# FET_Driver_Shunts.net
KiCad netlist of a schematic drawn in Altium Designer
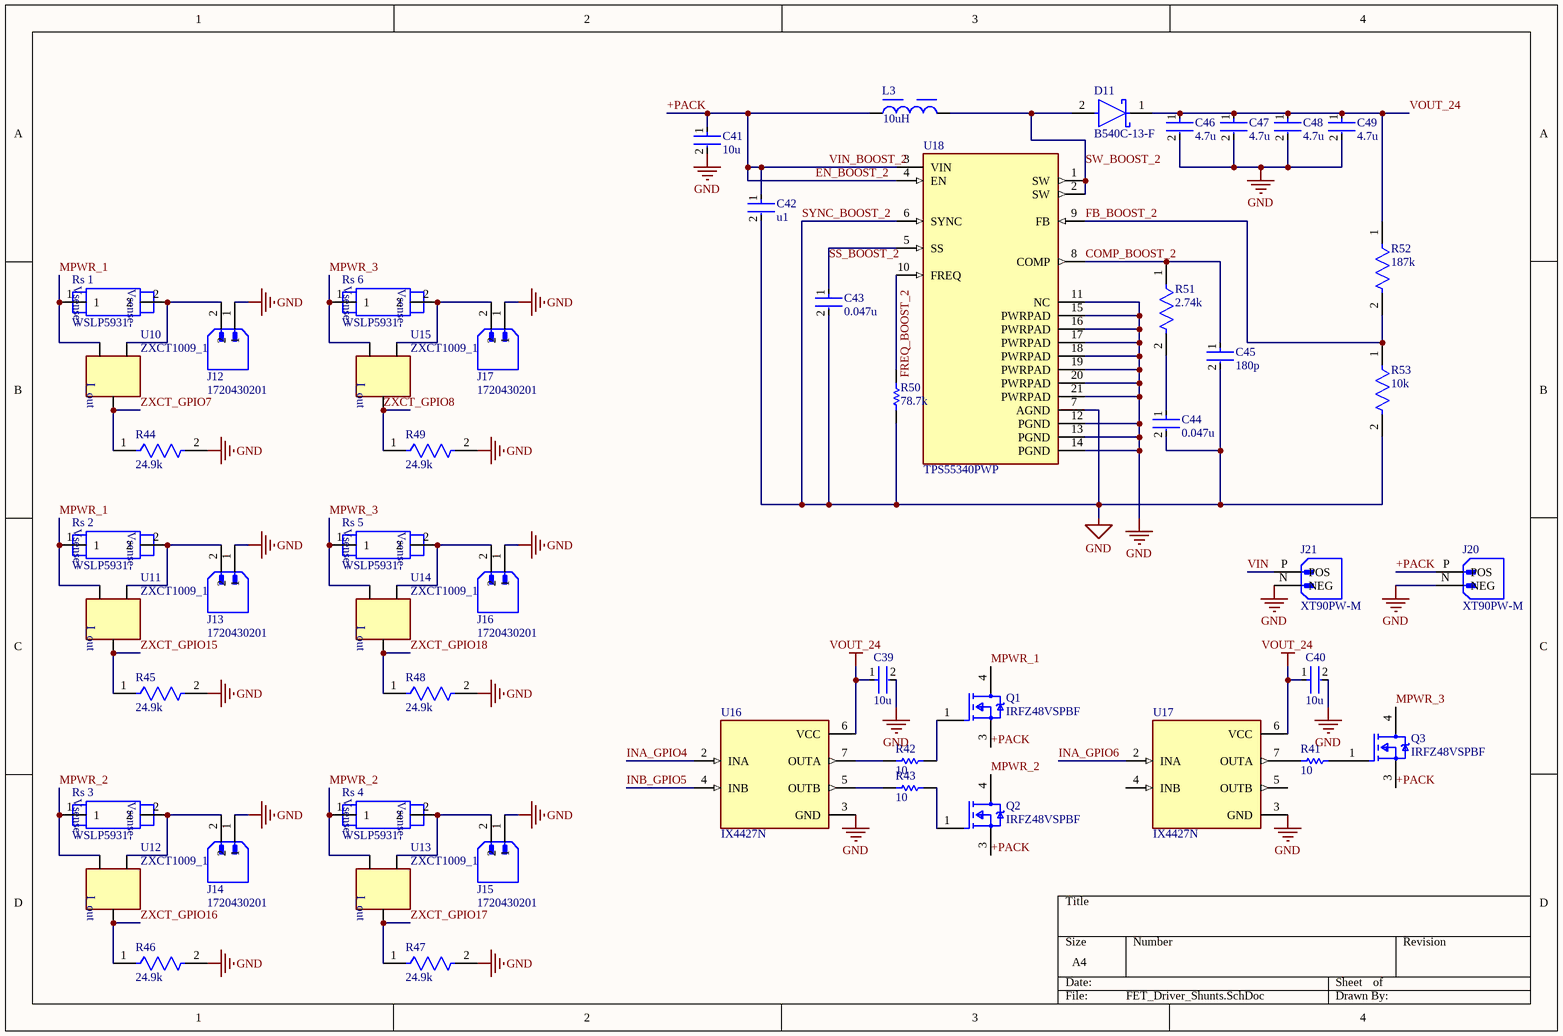
[diagram p0: FET_Driver_Shunts.SchDoc]

(export (version "E")
  (design (tool "Eeschema 10.0.6"))
  (components
    (comp (ref "C39")
      (value "10u")
      (footprint "FP-GRM21B-0_2-e0_2_0_7-MFG")
      (libsource (lib "Altium Content Vault") (part "b4654b650e69147ec39a6b967a45e02"))
    )
    (comp (ref "C40")
      (value "10u")
      (footprint "FP-GRM21B-0_2-e0_2_0_7-MFG")
      (libsource (lib "Altium Content Vault") (part "b4654b650e69147ec39a6b967a45e02"))
    )
    (comp (ref "C41")
      (value "10u")
      (footprint "FP-GRM21B-0_2-e0_2_0_7-MFG")
      (libsource (lib "Altium Content Vault") (part "b4654b650e69147ec39a6b967a45e02"))
    )
    (comp (ref "C42")
      (value "u1")
      (footprint "FP-CC0805-0_85-MFG")
      (description "CC0805KRX7R9BB104 CAP CER 0.1UF 50V X7R 0805")
      (fields (field (name "TOLERANCE") "0.1") (field (name "MANUFACTURER PART NUMBER") "CC0805KRX7R9BB104"))
      (libsource (lib "Altium Content Vault") (part "11868f565c42a9108669ba33697ecf6"))
    )
    (comp (ref "C43")
      (value "0.047u")
      (footprint "FP-C0805C-DN-MFG")
      (description "C0805C473K5RACTU  CAP CER 0.047UF 50V X7R 0805")
      (fields
        (field (name "MANUFACTURER PART NUMBER") "C0805C473K5RACTU")
        (field (name "OCTOPART") "https://octopart.com/c0805c473k5ractu-kemet-138387")
      )
      (libsource (lib "Altium Content Vault") (part "b4654b650e69147ec39a6b967a45e02"))
    )
    (comp (ref "C44")
      (value "0.047u")
      (footprint "FP-C0805C-DN-MFG")
      (description "C0805C473K5RACTU  CAP CER 0.047UF 50V X7R 0805")
      (fields
        (field (name "MANUFACTURER PART NUMBER") "C0805C473K5RACTU")
        (field (name "OCTOPART") "https://octopart.com/c0805c473k5ractu-kemet-138387")
      )
      (libsource (lib "Altium Content Vault") (part "b4654b650e69147ec39a6b967a45e02"))
    )
    (comp (ref "C45")
      (value "180p")
      (footprint "FP-C0805C-DN-MFG")
      (description "CAP CER 180PF 50V C0G/NP0 0805")
      (fields
        (field (name "MANUFACTURER") "KEMET")
        (field (name "OCTOPART") "https://octopart.com/c0805c181j5gactu-kemet-108653")
      )
      (libsource (lib "Altium Content Vault") (part "b4654b650e69147ec39a6b967a45e02"))
    )
    (comp (ref "C46")
      (value "4.7u")
      (footprint "FP-GRM32-MFG")
      (description "CAP CER 4.7UF 50V X7R 1210")
      (fields (field (name "MANUFACTURER") "Murata") (field (name "TOLERANCE") "10%"))
      (libsource (lib "Altium Content Vault") (part "b4654b650e69147ec39a6b967a45e02"))
    )
    (comp (ref "C47")
      (value "4.7u")
      (footprint "FP-GRM32-MFG")
      (description "CAP CER 4.7UF 50V X7R 1210")
      (fields (field (name "MANUFACTURER") "Murata") (field (name "TOLERANCE") "10%"))
      (libsource (lib "Altium Content Vault") (part "b4654b650e69147ec39a6b967a45e02"))
    )
    (comp (ref "C48")
      (value "4.7u")
      (footprint "FP-GRM32-MFG")
      (description "CAP CER 4.7UF 50V X7R 1210")
      (fields (field (name "MANUFACTURER") "Murata") (field (name "TOLERANCE") "10%"))
      (libsource (lib "Altium Content Vault") (part "b4654b650e69147ec39a6b967a45e02"))
    )
    (comp (ref "C49")
      (value "4.7u")
      (footprint "FP-GRM32-MFG")
      (description "CAP CER 4.7UF 50V X7R 1210")
      (fields (field (name "MANUFACTURER") "Murata") (field (name "TOLERANCE") "10%"))
      (libsource (lib "Altium Content Vault") (part "b4654b650e69147ec39a6b967a45e02"))
    )
    (comp (ref "D11")
      (value "B540C-13-F")
      (footprint "FP-SMC-MFG")
      (description "DIODE SCHOTTKY 40V 5A SMC")
      (fields
        (field (name "OCTOPART") "https://octopart.com/b540c-13-f-diodes+inc.-325873")
        (field (name "MANUFACTURER") "Diodes Inc.")
      )
      (libsource (lib "Altium Content Vault") (part "1d6ec82d83fb6aee721767c19dac4b9"))
    )
    (comp (ref "J12")
      (value "1720430201")
      (footprint "MOLEX_1720430201")
      (libsource (lib "PowerDistribution") (part "1720430201"))
    )
    (comp (ref "J13")
      (value "1720430201")
      (footprint "MOLEX_1720430201")
      (libsource (lib "PowerDistribution") (part "1720430201"))
    )
    (comp (ref "J14")
      (value "1720430201")
      (footprint "MOLEX_1720430201")
      (libsource (lib "PowerDistribution") (part "1720430201"))
    )
    (comp (ref "J15")
      (value "1720430201")
      (footprint "MOLEX_1720430201")
      (libsource (lib "PowerDistribution") (part "1720430201"))
    )
    (comp (ref "J16")
      (value "1720430201")
      (footprint "MOLEX_1720430201")
      (libsource (lib "PowerDistribution") (part "1720430201"))
    )
    (comp (ref "J17")
      (value "1720430201")
      (footprint "MOLEX_1720430201")
      (libsource (lib "PowerDistribution") (part "1720430201"))
    )
    (comp (ref "J20")
      (value "XT90PW-M")
      (footprint "AMASS_XT90PW-M")
      (description "Socket; DC supply; XT90; male; PIN: 2; on PCBs; THT; Colour: yellow")
      (fields (field (name "MF") "AMASS"))
      (libsource (lib "PowerDistribution") (part "XT90PW-M"))
    )
    (comp (ref "J21")
      (value "XT90PW-M")
      (footprint "AMASS_XT90PW-M")
      (description "Socket; DC supply; XT90; male; PIN: 2; on PCBs; THT; Colour: yellow")
      (fields (field (name "MF") "AMASS"))
      (libsource (lib "PowerDistribution") (part "XT90PW-M"))
    )
    (comp (ref "L3")
      (value "10uH")
      (footprint "WE-LHMI_1040")
      (fields (field (name "TOLERANCE") "20%"))
      (libsource (lib "Altium Content Vault") (part "Inductor - 3"))
    )
    (comp (ref "Q1")
      (value "IRFZ48VSPBF")
      (footprint "FP-IRFZ48VSPBF-MFG")
      (description "MOSFET N-CH 60V 72A D2PAK")
      (libsource (lib "Altium Content Vault") (part "e748bc7c0bda14637a9f13d1d571a93"))
    )
    (comp (ref "Q2")
      (value "IRFZ48VSPBF")
      (footprint "FP-IRFZ48VSPBF-MFG")
      (description "MOSFET N-CH 60V 72A D2PAK")
      (libsource (lib "Altium Content Vault") (part "e748bc7c0bda14637a9f13d1d571a93"))
    )
    (comp (ref "Q3")
      (value "IRFZ48VSPBF")
      (footprint "FP-IRFZ48VSPBF-MFG")
      (description "MOSFET N-CH 60V 72A D2PAK")
      (libsource (lib "Altium Content Vault") (part "e748bc7c0bda14637a9f13d1d571a93"))
    )
    (comp (ref "R41")
      (value "10")
      (footprint "RESC2013X50X30NL20T20")
      (description "CRCW080510R0FKEA")
      (fields (field (name "MANUFACTURER") "Vishay Dale"))
      (libsource (lib "Altium Content Vault") (part "RES"))
    )
    (comp (ref "R42")
      (value "10")
      (footprint "RESC2013X50X30NL20T20")
      (description "CRCW080510R0FKEA")
      (fields (field (name "MANUFACTURER") "Vishay Dale"))
      (libsource (lib "Altium Content Vault") (part "RES"))
    )
    (comp (ref "R43")
      (value "10")
      (footprint "RESC2013X50X30NL20T20")
      (description "CRCW080510R0FKEA")
      (fields (field (name "MANUFACTURER") "Vishay Dale"))
      (libsource (lib "Altium Content Vault") (part "RES"))
    )
    (comp (ref "R44")
      (value "24.9k")
      (footprint "FP-RMCF0805-IPC_A")
      (description "RMCF0805FT24K9  24.9kΩ ±1% 0.125W 0805 Thick Film Chip Resistor AEC-Q200 compliant")
      (fields (field (name "TOLERANCE") "1%"))
      (libsource (lib "Altium Content Vault") (part "1029c3af85768c4190bb7ad29bc67b5"))
    )
    (comp (ref "R45")
      (value "24.9k")
      (footprint "FP-RMCF0805-IPC_A")
      (description "RMCF0805FT24K9  24.9kΩ ±1% 0.125W 0805 Thick Film Chip Resistor AEC-Q200")
      (fields (field (name "TOLERANCE") "1%"))
      (libsource (lib "Altium Content Vault") (part "1029c3af85768c4190bb7ad29bc67b5"))
    )
    (comp (ref "R46")
      (value "24.9k")
      (footprint "FP-RMCF0805-IPC_A")
      (description "RMCF0805FT24K9  24.9kΩ ±1% 0.125W 0805 Thick Film Chip Resistor AEC-Q200")
      (fields (field (name "TOLERANCE") "1%"))
      (libsource (lib "Altium Content Vault") (part "1029c3af85768c4190bb7ad29bc67b5"))
    )
    (comp (ref "R47")
      (value "24.9k")
      (footprint "FP-RMCF0805-IPC_A")
      (description "RMCF0805FT24K9  24.9kΩ ±1% 0.125W 0805 Thick Film Chip Resistor AEC-Q200")
      (fields (field (name "TOLERANCE") "1%"))
      (libsource (lib "Altium Content Vault") (part "1029c3af85768c4190bb7ad29bc67b5"))
    )
    (comp (ref "R48")
      (value "24.9k")
      (footprint "FP-RMCF0805-IPC_A")
      (description "RMCF0805FT24K9  24.9kΩ ±1% 0.125W 0805 Thick Film Chip Resistor AEC-Q200")
      (fields (field (name "TOLERANCE") "1%"))
      (libsource (lib "Altium Content Vault") (part "1029c3af85768c4190bb7ad29bc67b5"))
    )
    (comp (ref "R49")
      (value "24.9k")
      (footprint "FP-RMCF0805-IPC_A")
      (description "RMCF0805FT24K9  24.9kΩ ±1% 0.125W 0805 Thick Film Chip Resistor AEC-Q200")
      (fields (field (name "TOLERANCE") "1%"))
      (libsource (lib "Altium Content Vault") (part "1029c3af85768c4190bb7ad29bc67b5"))
    )
    (comp (ref "R50")
      (value "78.7k")
      (footprint "RESC1608X55X30ML15T15")
      (fields (field (name "PART NUMBER") "ERJ-3EKF7872V") (field (name "MANUFACTURER") "Panasonic"))
      (libsource (lib "Altium Content Vault") (part "RES"))
    )
    (comp (ref "R51")
      (value "2.74k")
      (footprint "FP-CR0805-IPC_A")
      (description "Thick Film Chip Resistors 0805 2.74kΩ 0.125W 1% 100ppm/°C")
      (fields (field (name "TOLERANCE") "1%"))
      (libsource (lib "Altium Content Vault") (part "1029c3af85768c4190bb7ad29bc67b5"))
    )
    (comp (ref "R52")
      (value "187k")
      (footprint "FP-ERJ3EK-MFG")
      (description "RES SMD 187K OHM 1% 1/10W 0603")
      (fields (field (name "TOLERANCE") "1%"))
      (libsource (lib "Altium Content Vault") (part "1029c3af85768c4190bb7ad29bc67b5"))
    )
    (comp (ref "R53")
      (value "10k")
      (footprint "FP-ERA3A-IPC_C")
      (description "RES SMD 10K OHM 0.1% 1/10W 0603")
      (fields (field (name "TOLERANCE") "0.1%"))
      (libsource (lib "Altium Content Vault") (part "4e5f8b3dd332802e91518312df5df73"))
    )
    (comp (ref "Rs 1")
      (value "WSLP5931")
      (footprint "VISHAY_WSLP5931")
      (fields (field (name "MP") "WSLP59313L000FEB") (field (name "MF") "Vishay Dale"))
      (libsource (lib "PowerDistribution") (part "WSLP5931"))
    )
    (comp (ref "Rs 2")
      (value "WSLP5931")
      (footprint "VISHAY_WSLP5931")
      (fields (field (name "MP") "WSLP59313L000FEB") (field (name "MF") "Vishay Dale"))
      (libsource (lib "PowerDistribution") (part "WSLP5931"))
    )
    (comp (ref "Rs 3")
      (value "WSLP5931")
      (footprint "VISHAY_WSLP5931")
      (fields (field (name "MP") "WSLP59313L000FEB") (field (name "MF") "Vishay Dale"))
      (libsource (lib "PowerDistribution") (part "WSLP5931"))
    )
    (comp (ref "Rs 4")
      (value "WSLP5931")
      (footprint "VISHAY_WSLP5931")
      (fields (field (name "MP") "WSLP59313L000FEB") (field (name "MF") "Vishay Dale"))
      (libsource (lib "PowerDistribution") (part "WSLP5931"))
    )
    (comp (ref "Rs 5")
      (value "WSLP5931")
      (footprint "VISHAY_WSLP5931")
      (fields (field (name "MP") "WSLP59313L000FEB") (field (name "MF") "Vishay Dale"))
      (libsource (lib "PowerDistribution") (part "WSLP5931"))
    )
    (comp (ref "Rs 6")
      (value "WSLP5931")
      (footprint "VISHAY_WSLP5931")
      (fields (field (name "MP") "WSLP59313L000FEB") (field (name "MF") "Vishay Dale"))
      (libsource (lib "PowerDistribution") (part "WSLP5931"))
    )
    (comp (ref "U10")
      (value "ZXCT1009_1")
      (footprint "SOT23")
      (description "High Performance Current Monitor")
      (fields (field (name "MF") "Diodes Zetex") (field (name "MP") "ZXCT1009"))
      (libsource (lib "PowerDistribution") (part "ZXCT1009_1"))
    )
    (comp (ref "U11")
      (value "ZXCT1009_1")
      (footprint "SOT23")
      (description "High Performance Current Monitor")
      (fields (field (name "MF") "Diodes Zetex") (field (name "MP") "ZXCT1009"))
      (libsource (lib "PowerDistribution") (part "ZXCT1009_1"))
    )
    (comp (ref "U12")
      (value "ZXCT1009_1")
      (footprint "SOT23")
      (description "High Performance Current Monitor")
      (fields (field (name "MF") "Diodes Zetex") (field (name "MP") "ZXCT1009"))
      (libsource (lib "PowerDistribution") (part "ZXCT1009_1"))
    )
    (comp (ref "U13")
      (value "ZXCT1009_1")
      (footprint "SOT23")
      (description "High Performance Current Monitor")
      (fields (field (name "MF") "Diodes Zetex") (field (name "MP") "ZXCT1009"))
      (libsource (lib "PowerDistribution") (part "ZXCT1009_1"))
    )
    (comp (ref "U14")
      (value "ZXCT1009_1")
      (footprint "SOT23")
      (description "High Performance Current Monitor")
      (fields (field (name "MF") "Diodes Zetex") (field (name "MP") "ZXCT1009"))
      (libsource (lib "PowerDistribution") (part "ZXCT1009_1"))
    )
    (comp (ref "U15")
      (value "ZXCT1009_1")
      (footprint "SOT23")
      (description "High Performance Current Monitor")
      (fields (field (name "MF") "Diodes Zetex") (field (name "MP") "ZXCT1009"))
      (libsource (lib "PowerDistribution") (part "ZXCT1009_1"))
    )
    (comp (ref "U16")
      (value "IX4427N")
      (footprint "SOIC127P600X175-8N - duplicate")
      (description "Low-Side Gate Driver IC Non-Inverting 8-SOIC")
      (fields (field (name "MF") "IXYS Integrated"))
      (libsource (lib "PowerDistribution") (part "IX4427N"))
    )
    (comp (ref "U17")
      (value "IX4427N")
      (footprint "SOIC127P600X175-8N - duplicate")
      (description "Low-Side Gate Driver IC Non-Inverting 8-SOIC")
      (fields (field (name "MF") "IXYS Integrated"))
      (libsource (lib "PowerDistribution") (part "IX4427N"))
    )
    (comp (ref "U18")
      (value "TPS55340PWP")
      (footprint "IC_TPS55340PWP")
      (description "Integrated, 5-A 40-V Wide Input Range Boost/SEPIC/Flyback DC-DC Regulator 14-HTSSOP -40 to 150")
      (fields (field (name "MF") "Texas Instruments"))
      (libsource (lib "PowerDistribution") (part "TPS55340PWP"))
    )
  )
  (nets
    (net (code "1") (name "/+PACK") (class "Default")
      (node (ref "C41") (pin "1") (pinfunction "1_1") (pintype "passive"))
      (node (ref "C42") (pin "1") (pinfunction "1_1") (pintype "passive"))
      (node (ref "J20") (pin "P") (pinfunction "POS_P") (pintype "passive"))
      (node (ref "L3") (pin "1") (pinfunction "1_1") (pintype "passive"))
      (node (ref "Q1") (pin "3") (pinfunction "SOURCE_3") (pintype "passive"))
      (node (ref "Q2") (pin "3") (pinfunction "SOURCE_3") (pintype "passive"))
      (node (ref "Q3") (pin "3") (pinfunction "SOURCE_3") (pintype "passive"))
      (node (ref "U18") (pin "3") (pinfunction "VIN_3") (pintype "power_in"))
      (node (ref "U18") (pin "4") (pinfunction "EN_4") (pintype "input"))
    )
    (net (code "2") (name "/COMP_BOOST_2") (class "Default")
      (node (ref "C45") (pin "1") (pinfunction "1_1") (pintype "passive"))
      (node (ref "R51") (pin "1") (pinfunction "1_1") (pintype "passive"))
      (node (ref "U18") (pin "8") (pinfunction "COMP_8") (pintype "output"))
    )
    (net (code "3") (name "/FB_BOOST_2") (class "Default")
      (node (ref "R52") (pin "2") (pinfunction "2_2") (pintype "passive"))
      (node (ref "R53") (pin "1") (pinfunction "1_1") (pintype "passive"))
      (node (ref "U18") (pin "9") (pinfunction "FB_9") (pintype "input"))
    )
    (net (code "4") (name "/FREQ_BOOST_2") (class "Default")
      (node (ref "R50") (pin "2") (pinfunction "2_2") (pintype "passive"))
      (node (ref "U18") (pin "10") (pinfunction "FREQ_10") (pintype "input"))
    )
    (net (code "5") (name "/INA_GPIO4") (class "Default")
      (node (ref "U16") (pin "2") (pinfunction "INA_2") (pintype "input"))
    )
    (net (code "6") (name "/INA_GPIO6") (class "Default")
      (node (ref "U17") (pin "2") (pinfunction "INA_2") (pintype "input"))
    )
    (net (code "7") (name "/INB_GPIO5") (class "Default")
      (node (ref "U16") (pin "4") (pinfunction "INB_4") (pintype "input"))
    )
    (net (code "8") (name "/MPWR_1") (class "Default")
      (node (ref "Q1") (pin "4") (pinfunction "DRAIN_4") (pintype "passive"))
      (node (ref "Rs 1") (pin "1") (pinfunction "1_1") (pintype "passive"))
      (node (ref "Rs 2") (pin "1") (pinfunction "1_1") (pintype "passive"))
      (node (ref "U10") (pin "1") (pinfunction "VSENSE+_1") (pintype "bidirectional"))
      (node (ref "U11") (pin "1") (pinfunction "VSENSE+_1") (pintype "bidirectional"))
    )
    (net (code "9") (name "/MPWR_2") (class "Default")
      (node (ref "Q2") (pin "4") (pinfunction "DRAIN_4") (pintype "passive"))
      (node (ref "Rs 3") (pin "1") (pinfunction "1_1") (pintype "passive"))
      (node (ref "Rs 4") (pin "1") (pinfunction "1_1") (pintype "passive"))
      (node (ref "U12") (pin "1") (pinfunction "VSENSE+_1") (pintype "bidirectional"))
      (node (ref "U13") (pin "1") (pinfunction "VSENSE+_1") (pintype "bidirectional"))
    )
    (net (code "10") (name "/MPWR_3") (class "Default")
      (node (ref "Q3") (pin "4") (pinfunction "DRAIN_4") (pintype "passive"))
      (node (ref "Rs 5") (pin "1") (pinfunction "1_1") (pintype "passive"))
      (node (ref "Rs 6") (pin "1") (pinfunction "1_1") (pintype "passive"))
      (node (ref "U14") (pin "1") (pinfunction "VSENSE+_1") (pintype "bidirectional"))
      (node (ref "U15") (pin "1") (pinfunction "VSENSE+_1") (pintype "bidirectional"))
    )
    (net (code "11") (name "/SS_BOOST_2") (class "Default")
      (node (ref "C43") (pin "1") (pinfunction "1_1") (pintype "passive"))
      (node (ref "U18") (pin "5") (pinfunction "SS_5") (pintype "input"))
    )
    (net (code "12") (name "/SW_BOOST_2") (class "Default")
      (node (ref "D11") (pin "2") (pinfunction "A_2") (pintype "passive"))
      (node (ref "L3") (pin "2") (pinfunction "2_2") (pintype "passive"))
      (node (ref "U18") (pin "1") (pinfunction "SW_1") (pintype "output"))
      (node (ref "U18") (pin "2") (pinfunction "SW_2") (pintype "output"))
    )
    (net (code "13") (name "/VIN") (class "Default")
      (node (ref "J21") (pin "P") (pinfunction "POS_P") (pintype "passive"))
    )
    (net (code "14") (name "/ZXCT_GPIO7") (class "Default")
      (node (ref "R44") (pin "1") (pinfunction "1_1") (pintype "passive"))
      (node (ref "U10") (pin "3") (pinfunction "IOUT_3") (pintype "bidirectional"))
    )
    (net (code "15") (name "/ZXCT_GPIO8") (class "Default")
      (node (ref "R49") (pin "1") (pinfunction "1_1") (pintype "passive"))
      (node (ref "U15") (pin "3") (pinfunction "IOUT_3") (pintype "bidirectional"))
    )
    (net (code "16") (name "/ZXCT_GPIO15") (class "Default")
      (node (ref "R45") (pin "1") (pinfunction "1_1") (pintype "passive"))
      (node (ref "U11") (pin "3") (pinfunction "IOUT_3") (pintype "bidirectional"))
    )
    (net (code "17") (name "/ZXCT_GPIO16") (class "Default")
      (node (ref "R46") (pin "1") (pinfunction "1_1") (pintype "passive"))
      (node (ref "U12") (pin "3") (pinfunction "IOUT_3") (pintype "bidirectional"))
    )
    (net (code "18") (name "/ZXCT_GPIO17") (class "Default")
      (node (ref "R47") (pin "1") (pinfunction "1_1") (pintype "passive"))
      (node (ref "U13") (pin "3") (pinfunction "IOUT_3") (pintype "bidirectional"))
    )
    (net (code "19") (name "/ZXCT_GPIO18") (class "Default")
      (node (ref "R48") (pin "1") (pinfunction "1_1") (pintype "passive"))
      (node (ref "U14") (pin "3") (pinfunction "IOUT_3") (pintype "bidirectional"))
    )
    (net (code "20") (name "GND") (class "Default")
      (node (ref "C39") (pin "2") (pinfunction "2_2") (pintype "passive"))
      (node (ref "C40") (pin "2") (pinfunction "2_2") (pintype "passive"))
      (node (ref "C41") (pin "2") (pinfunction "2_2") (pintype "passive"))
      (node (ref "C42") (pin "2") (pinfunction "2_2") (pintype "passive"))
      (node (ref "C43") (pin "2") (pinfunction "2_2") (pintype "passive"))
      (node (ref "C44") (pin "2") (pinfunction "2_2") (pintype "passive"))
      (node (ref "C45") (pin "2") (pinfunction "2_2") (pintype "passive"))
      (node (ref "C46") (pin "2") (pinfunction "2_2") (pintype "passive"))
      (node (ref "C47") (pin "2") (pinfunction "2_2") (pintype "passive"))
      (node (ref "C48") (pin "2") (pinfunction "2_2") (pintype "passive"))
      (node (ref "C49") (pin "2") (pinfunction "2_2") (pintype "passive"))
      (node (ref "J12") (pin "1") (pinfunction "1_1") (pintype "passive"))
      (node (ref "J13") (pin "1") (pinfunction "1_1") (pintype "passive"))
      (node (ref "J14") (pin "1") (pinfunction "1_1") (pintype "passive"))
      (node (ref "J15") (pin "1") (pinfunction "1_1") (pintype "passive"))
      (node (ref "J16") (pin "1") (pinfunction "1_1") (pintype "passive"))
      (node (ref "J17") (pin "1") (pinfunction "1_1") (pintype "passive"))
      (node (ref "J20") (pin "N") (pinfunction "NEG_N") (pintype "passive"))
      (node (ref "J21") (pin "N") (pinfunction "NEG_N") (pintype "passive"))
      (node (ref "R44") (pin "2") (pinfunction "2_2") (pintype "passive"))
      (node (ref "R45") (pin "2") (pinfunction "2_2") (pintype "passive"))
      (node (ref "R46") (pin "2") (pinfunction "2_2") (pintype "passive"))
      (node (ref "R47") (pin "2") (pinfunction "2_2") (pintype "passive"))
      (node (ref "R48") (pin "2") (pinfunction "2_2") (pintype "passive"))
      (node (ref "R49") (pin "2") (pinfunction "2_2") (pintype "passive"))
      (node (ref "R50") (pin "1") (pinfunction "1_1") (pintype "passive"))
      (node (ref "R53") (pin "2") (pinfunction "2_2") (pintype "passive"))
      (node (ref "U16") (pin "3") (pinfunction "GND_3") (pintype "power_in"))
      (node (ref "U17") (pin "3") (pinfunction "GND_3") (pintype "power_in"))
      (node (ref "U18") (pin "11") (pinfunction "NC_11") (pintype "power_in"))
      (node (ref "U18") (pin "12") (pinfunction "PGND_12") (pintype "power_in"))
      (node (ref "U18") (pin "13") (pinfunction "PGND_13") (pintype "power_in"))
      (node (ref "U18") (pin "14") (pinfunction "PGND_14") (pintype "power_in"))
      (node (ref "U18") (pin "15") (pinfunction "PWRPAD_15") (pintype "power_in"))
      (node (ref "U18") (pin "16") (pinfunction "PWRPAD_16") (pintype "power_in"))
      (node (ref "U18") (pin "17") (pinfunction "PWRPAD_17") (pintype "power_in"))
      (node (ref "U18") (pin "18") (pinfunction "PWRPAD_18") (pintype "power_in"))
      (node (ref "U18") (pin "19") (pinfunction "PWRPAD_19") (pintype "power_in"))
      (node (ref "U18") (pin "20") (pinfunction "PWRPAD_20") (pintype "power_in"))
      (node (ref "U18") (pin "21") (pinfunction "PWRPAD_21") (pintype "power_in"))
      (node (ref "U18") (pin "6") (pinfunction "SYNC_6") (pintype "input"))
      (node (ref "U18") (pin "7") (pinfunction "AGND_7") (pintype "power_in"))
    )
    (net (code "21") (name "Net-(C44-Pad1)") (class "Default")
      (node (ref "C44") (pin "1") (pinfunction "1_1") (pintype "passive"))
      (node (ref "R51") (pin "2") (pinfunction "2_2") (pintype "passive"))
    )
    (net (code "22") (name "Net-(Q1-GATE)") (class "Default")
      (node (ref "Q1") (pin "1") (pinfunction "GATE_1") (pintype "passive"))
      (node (ref "R42") (pin "2") (pinfunction "2_2") (pintype "passive"))
    )
    (net (code "23") (name "Net-(Q2-GATE)") (class "Default")
      (node (ref "Q2") (pin "1") (pinfunction "GATE_1") (pintype "passive"))
      (node (ref "R43") (pin "2") (pinfunction "2_2") (pintype "passive"))
    )
    (net (code "24") (name "Net-(Q3-GATE)") (class "Default")
      (node (ref "Q3") (pin "1") (pinfunction "GATE_1") (pintype "passive"))
      (node (ref "R41") (pin "2") (pinfunction "2_2") (pintype "passive"))
    )
    (net (code "25") (name "Net-(U10-VSENSE-)") (class "Default")
      (node (ref "J12") (pin "2") (pinfunction "2_2") (pintype "passive"))
      (node (ref "Rs 1") (pin "2") (pinfunction "2_2") (pintype "passive"))
      (node (ref "U10") (pin "2") (pinfunction "VSENSE-_2") (pintype "bidirectional"))
    )
    (net (code "26") (name "Net-(U11-VSENSE-)") (class "Default")
      (node (ref "J13") (pin "2") (pinfunction "2_2") (pintype "passive"))
      (node (ref "Rs 2") (pin "2") (pinfunction "2_2") (pintype "passive"))
      (node (ref "U11") (pin "2") (pinfunction "VSENSE-_2") (pintype "bidirectional"))
    )
    (net (code "27") (name "Net-(U12-VSENSE-)") (class "Default")
      (node (ref "J14") (pin "2") (pinfunction "2_2") (pintype "passive"))
      (node (ref "Rs 3") (pin "2") (pinfunction "2_2") (pintype "passive"))
      (node (ref "U12") (pin "2") (pinfunction "VSENSE-_2") (pintype "bidirectional"))
    )
    (net (code "28") (name "Net-(U13-VSENSE-)") (class "Default")
      (node (ref "J15") (pin "2") (pinfunction "2_2") (pintype "passive"))
      (node (ref "Rs 4") (pin "2") (pinfunction "2_2") (pintype "passive"))
      (node (ref "U13") (pin "2") (pinfunction "VSENSE-_2") (pintype "bidirectional"))
    )
    (net (code "29") (name "Net-(U14-VSENSE-)") (class "Default")
      (node (ref "J16") (pin "2") (pinfunction "2_2") (pintype "passive"))
      (node (ref "Rs 5") (pin "2") (pinfunction "2_2") (pintype "passive"))
      (node (ref "U14") (pin "2") (pinfunction "VSENSE-_2") (pintype "bidirectional"))
    )
    (net (code "30") (name "Net-(U15-VSENSE-)") (class "Default")
      (node (ref "J17") (pin "2") (pinfunction "2_2") (pintype "passive"))
      (node (ref "Rs 6") (pin "2") (pinfunction "2_2") (pintype "passive"))
      (node (ref "U15") (pin "2") (pinfunction "VSENSE-_2") (pintype "bidirectional"))
    )
    (net (code "31") (name "Net-(U16-OUTA)") (class "Default")
      (node (ref "R42") (pin "1") (pinfunction "1_1") (pintype "passive"))
      (node (ref "U16") (pin "7") (pinfunction "OUTA_7") (pintype "output"))
    )
    (net (code "32") (name "Net-(U16-OUTB)") (class "Default")
      (node (ref "R43") (pin "1") (pinfunction "1_1") (pintype "passive"))
      (node (ref "U16") (pin "5") (pinfunction "OUTB_5") (pintype "output"))
    )
    (net (code "33") (name "Net-(U17-OUTA)") (class "Default")
      (node (ref "R41") (pin "1") (pinfunction "1_1") (pintype "passive"))
      (node (ref "U17") (pin "7") (pinfunction "OUTA_7") (pintype "output"))
    )
    (net (code "34") (name "VOUT_24") (class "Default")
      (node (ref "C39") (pin "1") (pinfunction "1_1") (pintype "passive"))
      (node (ref "C40") (pin "1") (pinfunction "1_1") (pintype "passive"))
      (node (ref "C46") (pin "1") (pinfunction "1_1") (pintype "passive"))
      (node (ref "C47") (pin "1") (pinfunction "1_1") (pintype "passive"))
      (node (ref "C48") (pin "1") (pinfunction "1_1") (pintype "passive"))
      (node (ref "C49") (pin "1") (pinfunction "1_1") (pintype "passive"))
      (node (ref "D11") (pin "1") (pinfunction "C_1") (pintype "passive"))
      (node (ref "R52") (pin "1") (pinfunction "1_1") (pintype "passive"))
      (node (ref "U16") (pin "6") (pinfunction "VCC_6") (pintype "power_in"))
      (node (ref "U17") (pin "6") (pinfunction "VCC_6") (pintype "power_in"))
    )
    (net (code "35") (name "unconnected-(U17-INB-Pad4)") (class "Default")
      (node (ref "U17") (pin "4") (pinfunction "INB_4") (pintype "input"))
    )
    (net (code "36") (name "unconnected-(U17-OUTB-Pad5)") (class "Default")
      (node (ref "U17") (pin "5") (pinfunction "OUTB_5") (pintype "output"))
    )
  )
)
